# LED_Ring_v8.net
KiCad netlist of a schematic drawn in EAGLE
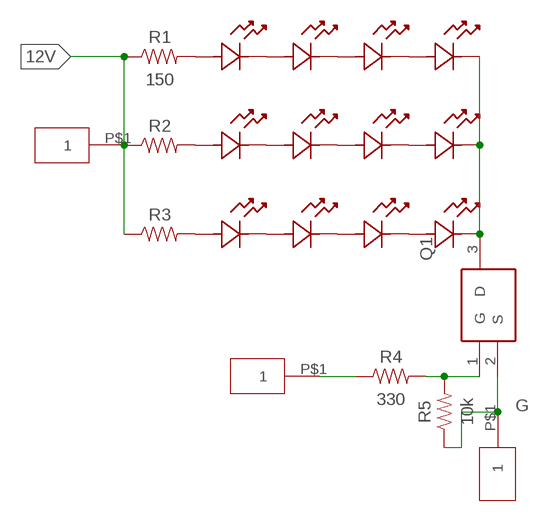
[diagram p0: schematic, sheet 1]

(export (version "E")
  (design (tool "Eeschema 10.0.6"))
  (components
    (comp (ref "LED5")
      (value "GW_JTLMS1.EM-GWH4-XX53-1-60-R3LED_SMT-GWJTLMS1.EM_AOS")
      (footprint "eagle-import:LED_SMT-GWJTLMS1.EM_AOS")
      (fields
        (field (name "MANUFACTURER_PART_NUMBER") "GW JTLMS1.EM-GWH4-XX53-1-60-R33")
        (field (name "COPYRIGHT") "Copyright (C) 2025 Ultra Librarian. All rights reserved.")
      )
      (libsource (lib "eagle-import") (part "GW_JTLMS1.EM-GWH4-XX53-1-60-R3LED_SMT-GWJTLMS1.EM_AOS"))
    )
    (comp (ref "LED6")
      (value "GW_JTLMS1.EM-GWH4-XX53-1-60-R3LED_SMT-GWJTLMS1.EM_AOS")
      (footprint "eagle-import:LED_SMT-GWJTLMS1.EM_AOS")
      (fields
        (field (name "MANUFACTURER_PART_NUMBER") "GW JTLMS1.EM-GWH4-XX53-1-60-R33")
        (field (name "COPYRIGHT") "Copyright (C) 2025 Ultra Librarian. All rights reserved.")
      )
      (libsource (lib "eagle-import") (part "GW_JTLMS1.EM-GWH4-XX53-1-60-R3LED_SMT-GWJTLMS1.EM_AOS"))
    )
    (comp (ref "LED7")
      (value "GW_JTLMS1.EM-GWH4-XX53-1-60-R3LED_SMT-GWJTLMS1.EM_AOS")
      (footprint "eagle-import:LED_SMT-GWJTLMS1.EM_AOS")
      (fields
        (field (name "MANUFACTURER_PART_NUMBER") "GW JTLMS1.EM-GWH4-XX53-1-60-R33")
        (field (name "COPYRIGHT") "Copyright (C) 2025 Ultra Librarian. All rights reserved.")
      )
      (libsource (lib "eagle-import") (part "GW_JTLMS1.EM-GWH4-XX53-1-60-R3LED_SMT-GWJTLMS1.EM_AOS"))
    )
    (comp (ref "LED8")
      (value "GW_JTLMS1.EM-GWH4-XX53-1-60-R3LED_SMT-GWJTLMS1.EM_AOS")
      (footprint "eagle-import:LED_SMT-GWJTLMS1.EM_AOS")
      (fields
        (field (name "MANUFACTURER_PART_NUMBER") "GW JTLMS1.EM-GWH4-XX53-1-60-R33")
        (field (name "COPYRIGHT") "Copyright (C) 2025 Ultra Librarian. All rights reserved.")
      )
      (libsource (lib "eagle-import") (part "GW_JTLMS1.EM-GWH4-XX53-1-60-R3LED_SMT-GWJTLMS1.EM_AOS"))
    )
    (comp (ref "LED9")
      (value "GW_JTLMS1.EM-GWH4-XX53-1-60-R3LED_SMT-GWJTLMS1.EM_AOS")
      (footprint "eagle-import:LED_SMT-GWJTLMS1.EM_AOS")
      (fields
        (field (name "MANUFACTURER_PART_NUMBER") "GW JTLMS1.EM-GWH4-XX53-1-60-R33")
        (field (name "COPYRIGHT") "Copyright (C) 2025 Ultra Librarian. All rights reserved.")
      )
      (libsource (lib "eagle-import") (part "GW_JTLMS1.EM-GWH4-XX53-1-60-R3LED_SMT-GWJTLMS1.EM_AOS"))
    )
    (comp (ref "LED10")
      (value "GW_JTLMS1.EM-GWH4-XX53-1-60-R3LED_SMT-GWJTLMS1.EM_AOS")
      (footprint "eagle-import:LED_SMT-GWJTLMS1.EM_AOS")
      (fields
        (field (name "MANUFACTURER_PART_NUMBER") "GW JTLMS1.EM-GWH4-XX53-1-60-R33")
        (field (name "COPYRIGHT") "Copyright (C) 2025 Ultra Librarian. All rights reserved.")
      )
      (libsource (lib "eagle-import") (part "GW_JTLMS1.EM-GWH4-XX53-1-60-R3LED_SMT-GWJTLMS1.EM_AOS"))
    )
    (comp (ref "LED11")
      (value "GW_JTLMS1.EM-GWH4-XX53-1-60-R3LED_SMT-GWJTLMS1.EM_AOS")
      (footprint "eagle-import:LED_SMT-GWJTLMS1.EM_AOS")
      (fields
        (field (name "MANUFACTURER_PART_NUMBER") "GW JTLMS1.EM-GWH4-XX53-1-60-R33")
        (field (name "COPYRIGHT") "Copyright (C) 2025 Ultra Librarian. All rights reserved.")
      )
      (libsource (lib "eagle-import") (part "GW_JTLMS1.EM-GWH4-XX53-1-60-R3LED_SMT-GWJTLMS1.EM_AOS"))
    )
    (comp (ref "LED12")
      (value "GW_JTLMS1.EM-GWH4-XX53-1-60-R3LED_SMT-GWJTLMS1.EM_AOS")
      (footprint "eagle-import:LED_SMT-GWJTLMS1.EM_AOS")
      (fields
        (field (name "MANUFACTURER_PART_NUMBER") "GW JTLMS1.EM-GWH4-XX53-1-60-R33")
        (field (name "COPYRIGHT") "Copyright (C) 2025 Ultra Librarian. All rights reserved.")
      )
      (libsource (lib "eagle-import") (part "GW_JTLMS1.EM-GWH4-XX53-1-60-R3LED_SMT-GWJTLMS1.EM_AOS"))
    )
    (comp (ref "LED13")
      (value "GW_JTLMS1.EM-GWH4-XX53-1-60-R3LED_SMT-GWJTLMS1.EM_AOS")
      (footprint "eagle-import:LED_SMT-GWJTLMS1.EM_AOS")
      (fields
        (field (name "MANUFACTURER_PART_NUMBER") "GW JTLMS1.EM-GWH4-XX53-1-60-R33")
        (field (name "COPYRIGHT") "Copyright (C) 2025 Ultra Librarian. All rights reserved.")
      )
      (libsource (lib "eagle-import") (part "GW_JTLMS1.EM-GWH4-XX53-1-60-R3LED_SMT-GWJTLMS1.EM_AOS"))
    )
    (comp (ref "LED14")
      (value "GW_JTLMS1.EM-GWH4-XX53-1-60-R3LED_SMT-GWJTLMS1.EM_AOS")
      (footprint "eagle-import:LED_SMT-GWJTLMS1.EM_AOS")
      (fields
        (field (name "MANUFACTURER_PART_NUMBER") "GW JTLMS1.EM-GWH4-XX53-1-60-R33")
        (field (name "COPYRIGHT") "Copyright (C) 2025 Ultra Librarian. All rights reserved.")
      )
      (libsource (lib "eagle-import") (part "GW_JTLMS1.EM-GWH4-XX53-1-60-R3LED_SMT-GWJTLMS1.EM_AOS"))
    )
    (comp (ref "LED15")
      (value "GW_JTLMS1.EM-GWH4-XX53-1-60-R3LED_SMT-GWJTLMS1.EM_AOS")
      (footprint "eagle-import:LED_SMT-GWJTLMS1.EM_AOS")
      (fields
        (field (name "MANUFACTURER_PART_NUMBER") "GW JTLMS1.EM-GWH4-XX53-1-60-R33")
        (field (name "COPYRIGHT") "Copyright (C) 2025 Ultra Librarian. All rights reserved.")
      )
      (libsource (lib "eagle-import") (part "GW_JTLMS1.EM-GWH4-XX53-1-60-R3LED_SMT-GWJTLMS1.EM_AOS"))
    )
    (comp (ref "LED16")
      (value "GW_JTLMS1.EM-GWH4-XX53-1-60-R3LED_SMT-GWJTLMS1.EM_AOS")
      (footprint "eagle-import:LED_SMT-GWJTLMS1.EM_AOS")
      (fields
        (field (name "MANUFACTURER_PART_NUMBER") "GW JTLMS1.EM-GWH4-XX53-1-60-R33")
        (field (name "COPYRIGHT") "Copyright (C) 2025 Ultra Librarian. All rights reserved.")
      )
      (libsource (lib "eagle-import") (part "GW_JTLMS1.EM-GWH4-XX53-1-60-R3LED_SMT-GWJTLMS1.EM_AOS"))
    )
    (comp (ref "Q1")
      (value "IRLML6244TRPBF")
      (footprint "eagle-import:SOT95P237X112-3N")
      (fields (field (name "MOUSER_PART_NUMBER") "942-IRLML6244TRPBF"))
      (libsource (lib "eagle-import") (part "IRLML6244TRPBF"))
    )
    (comp (ref "R1")
      (value "150")
      (footprint "eagle-import:RESC1005X40")
      (libsource (lib "eagle-import") (part "R-USCHIP-0402(1005-METRIC)_"))
    )
    (comp (ref "R2")
      (value "R-US_CHIP-0402(1005-METRIC)")
      (footprint "eagle-import:RESC1005X40")
      (libsource (lib "eagle-import") (part "R-USCHIP-0402(1005-METRIC)_"))
    )
    (comp (ref "R3")
      (value "R-US_CHIP-0402(1005-METRIC)")
      (footprint "eagle-import:RESC1005X40")
      (libsource (lib "eagle-import") (part "R-USCHIP-0402(1005-METRIC)_"))
    )
    (comp (ref "R4")
      (value "330")
      (footprint "eagle-import:RESC1005X40")
      (libsource (lib "eagle-import") (part "R-USCHIP-0402(1005-METRIC)_"))
    )
    (comp (ref "R5")
      (value "10k")
      (footprint "eagle-import:RESC1005X40")
      (libsource (lib "eagle-import") (part "R-USCHIP-0402(1005-METRIC)_"))
    )
    (comp (ref "U$1")
      (value "SOLDER_PAD_HOLE")
      (footprint "eagle-import:SOLDER_PAD_HOLE")
      (libsource (lib "eagle-import") (part "SOLDER_PAD_HOLE"))
    )
    (comp (ref "U$2")
      (value "SOLDER_PAD_HOLE")
      (footprint "eagle-import:SOLDER_PAD_HOLE")
      (libsource (lib "eagle-import") (part "SOLDER_PAD_HOLE"))
    )
    (comp (ref "U$3")
      (value "SOLDER_PAD_HOLE")
      (footprint "eagle-import:SOLDER_PAD_HOLE")
      (libsource (lib "eagle-import") (part "SOLDER_PAD_HOLE"))
    )
  )
  (nets
    (net (code "1") (name "/G") (class "Default")
      (node (ref "Q1") (pin "2") (pinfunction "S_2") (pintype "bidirectional"))
      (node (ref "R5") (pin "1") (pinfunction "1_1") (pintype "passive"))
      (node (ref "U$2") (pin "P$1") (pinfunction "1_P$1") (pintype "bidirectional"))
    )
    (net (code "2") (name "12V") (class "Default")
      (node (ref "R1") (pin "1") (pinfunction "1_1") (pintype "passive"))
      (node (ref "R2") (pin "1") (pinfunction "1_1") (pintype "passive"))
      (node (ref "R3") (pin "1") (pinfunction "1_1") (pintype "passive"))
      (node (ref "U$1") (pin "P$1") (pinfunction "1_P$1") (pintype "bidirectional"))
    )
    (net (code "3") (name "Net-(LED5-Pad1)") (class "Default")
      (node (ref "LED5") (pin "1") (pinfunction "1_1") (pintype "passive"))
      (node (ref "LED6") (pin "2") (pinfunction "2_2") (pintype "passive"))
    )
    (net (code "4") (name "Net-(LED5-Pad2)") (class "Default")
      (node (ref "LED5") (pin "2") (pinfunction "2_2") (pintype "passive"))
      (node (ref "R3") (pin "2") (pinfunction "2_2") (pintype "passive"))
    )
    (net (code "5") (name "Net-(LED6-Pad1)") (class "Default")
      (node (ref "LED6") (pin "1") (pinfunction "1_1") (pintype "passive"))
      (node (ref "LED7") (pin "2") (pinfunction "2_2") (pintype "passive"))
    )
    (net (code "6") (name "Net-(LED7-Pad1)") (class "Default")
      (node (ref "LED7") (pin "1") (pinfunction "1_1") (pintype "passive"))
      (node (ref "LED8") (pin "2") (pinfunction "2_2") (pintype "passive"))
    )
    (net (code "7") (name "Net-(LED9-Pad2)") (class "Default")
      (node (ref "LED9") (pin "2") (pinfunction "2_2") (pintype "passive"))
      (node (ref "R2") (pin "2") (pinfunction "2_2") (pintype "passive"))
    )
    (net (code "8") (name "Net-(LED10-Pad1)") (class "Default")
      (node (ref "LED10") (pin "1") (pinfunction "1_1") (pintype "passive"))
      (node (ref "LED11") (pin "2") (pinfunction "2_2") (pintype "passive"))
    )
    (net (code "9") (name "Net-(LED10-Pad2)") (class "Default")
      (node (ref "LED10") (pin "2") (pinfunction "2_2") (pintype "passive"))
      (node (ref "LED9") (pin "1") (pinfunction "1_1") (pintype "passive"))
    )
    (net (code "10") (name "Net-(LED11-Pad1)") (class "Default")
      (node (ref "LED11") (pin "1") (pinfunction "1_1") (pintype "passive"))
      (node (ref "LED12") (pin "2") (pinfunction "2_2") (pintype "passive"))
    )
    (net (code "11") (name "Net-(LED13-Pad1)") (class "Default")
      (node (ref "LED13") (pin "1") (pinfunction "1_1") (pintype "passive"))
      (node (ref "LED14") (pin "2") (pinfunction "2_2") (pintype "passive"))
    )
    (net (code "12") (name "Net-(LED13-Pad2)") (class "Default")
      (node (ref "LED13") (pin "2") (pinfunction "2_2") (pintype "passive"))
      (node (ref "R1") (pin "2") (pinfunction "2_2") (pintype "passive"))
    )
    (net (code "13") (name "Net-(LED14-Pad1)") (class "Default")
      (node (ref "LED14") (pin "1") (pinfunction "1_1") (pintype "passive"))
      (node (ref "LED15") (pin "2") (pinfunction "2_2") (pintype "passive"))
    )
    (net (code "14") (name "Net-(LED15-Pad1)") (class "Default")
      (node (ref "LED15") (pin "1") (pinfunction "1_1") (pintype "passive"))
      (node (ref "LED16") (pin "2") (pinfunction "2_2") (pintype "passive"))
    )
    (net (code "15") (name "Net-(Q1-D)") (class "Default")
      (node (ref "LED12") (pin "1") (pinfunction "1_1") (pintype "passive"))
      (node (ref "LED16") (pin "1") (pinfunction "1_1") (pintype "passive"))
      (node (ref "LED8") (pin "1") (pinfunction "1_1") (pintype "passive"))
      (node (ref "Q1") (pin "3") (pinfunction "D_3") (pintype "bidirectional"))
    )
    (net (code "16") (name "Net-(Q1-G)") (class "Default")
      (node (ref "Q1") (pin "1") (pinfunction "G_1") (pintype "bidirectional"))
      (node (ref "R4") (pin "2") (pinfunction "2_2") (pintype "passive"))
      (node (ref "R5") (pin "2") (pinfunction "2_2") (pintype "passive"))
    )
    (net (code "17") (name "Net-(U$3-1)") (class "Default")
      (node (ref "R4") (pin "1") (pinfunction "1_1") (pintype "passive"))
      (node (ref "U$3") (pin "P$1") (pinfunction "1_P$1") (pintype "bidirectional"))
    )
  )
)
